# ZHSD-PL-CONNS.net
KiCad netlist of a schematic drawn in Altium Designer
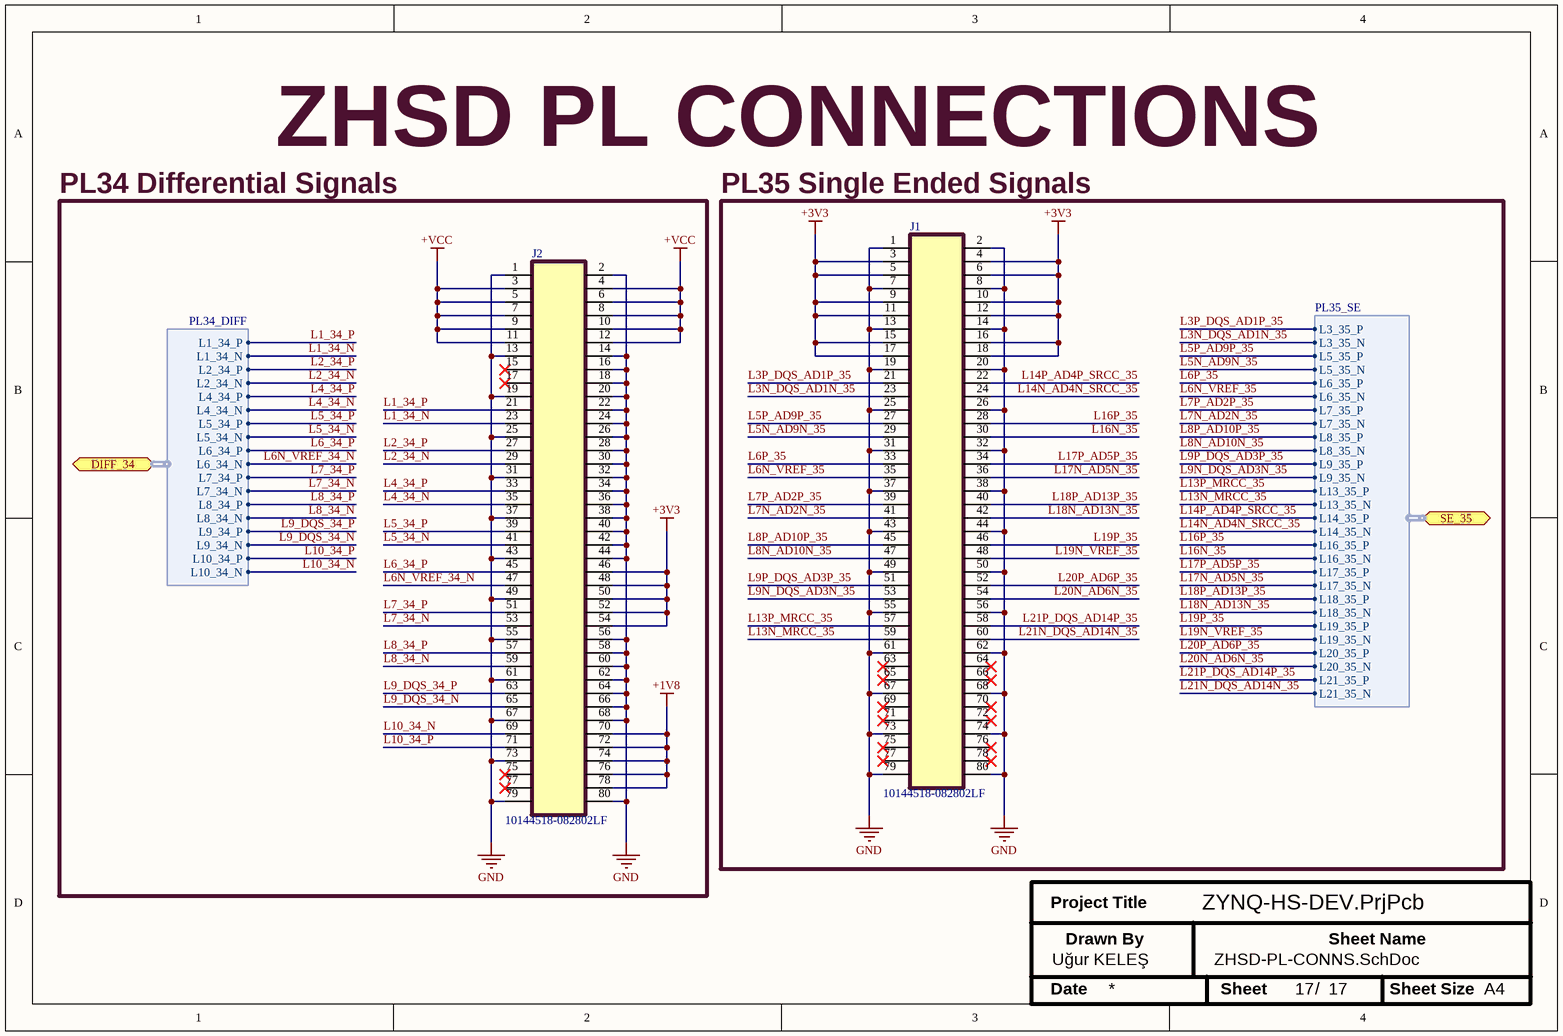
[diagram p0: ZHSD-PL-CONNS.SchDoc]

(export (version "E")
  (design (tool "Eeschema 10.0.6"))
  (components
    (comp (ref "J1")
      (value "10144518-082802LF")
      (footprint "10144518-082802LF")
      (description "BergStak® Lite 0.80mm, Board-to-Board Connector, 80 Positions, Dual Row, Vertical Header")
      (fields (field (name "MANUFACTURER") "Amphenol"))
      (libsource (lib "UK_Library") (part "10144518-082802LF"))
    )
    (comp (ref "J2")
      (value "10144518-082802LF")
      (footprint "10144518-082802LF")
      (description "BergStak® Lite 0.80mm, Board-to-Board Connector, 80 Positions, Dual Row, Vertical Header")
      (fields (field (name "MANUFACTURER") "Amphenol"))
      (libsource (lib "UK_Library") (part "10144518-082802LF"))
    )
  )
  (nets
    (net (code "3") (name "+1V8") (class "Default")
      (node (ref "J2") (pin "70") (pintype "passive"))
      (node (ref "J2") (pin "72") (pintype "passive"))
      (node (ref "J2") (pin "74") (pintype "passive"))
      (node (ref "J2") (pin "76") (pintype "passive"))
      (node (ref "J2") (pin "78") (pintype "passive"))
    )
    (net (code "4") (name "+3V3") (class "Default")
      (node (ref "J1") (pin "10") (pintype "passive"))
      (node (ref "J1") (pin "11") (pintype "passive"))
      (node (ref "J1") (pin "12") (pintype "passive"))
      (node (ref "J1") (pin "15") (pintype "passive"))
      (node (ref "J1") (pin "16") (pintype "passive"))
      (node (ref "J1") (pin "17") (pintype "passive"))
      (node (ref "J1") (pin "18") (pintype "passive"))
      (node (ref "J1") (pin "3") (pintype "passive"))
      (node (ref "J1") (pin "4") (pintype "passive"))
      (node (ref "J1") (pin "5") (pintype "passive"))
      (node (ref "J1") (pin "6") (pintype "passive"))
      (node (ref "J1") (pin "9") (pintype "passive"))
      (node (ref "J2") (pin "46") (pintype "passive"))
      (node (ref "J2") (pin "48") (pintype "passive"))
      (node (ref "J2") (pin "50") (pintype "passive"))
      (node (ref "J2") (pin "52") (pintype "passive"))
      (node (ref "J2") (pin "54") (pintype "passive"))
    )
    (net (code "5") (name "+VCC") (class "Default")
      (node (ref "J2") (pin "10") (pintype "passive"))
      (node (ref "J2") (pin "11") (pintype "passive"))
      (node (ref "J2") (pin "12") (pintype "passive"))
      (node (ref "J2") (pin "3") (pintype "passive"))
      (node (ref "J2") (pin "4") (pintype "passive"))
      (node (ref "J2") (pin "5") (pintype "passive"))
      (node (ref "J2") (pin "6") (pintype "passive"))
      (node (ref "J2") (pin "7") (pintype "passive"))
      (node (ref "J2") (pin "8") (pintype "passive"))
      (node (ref "J2") (pin "9") (pintype "passive"))
    )
    (net (code "6") (name "/L1_34_N") (class "Default") (node (ref "J2") (pin "23") (pintype "passive")))
    (net (code "7") (name "/L1_34_P") (class "Default") (node (ref "J2") (pin "21") (pintype "passive")))
    (net (code "8") (name "/L2_34_N") (class "Default") (node (ref "J2") (pin "29") (pintype "passive")))
    (net (code "9") (name "/L2_34_P") (class "Default") (node (ref "J2") (pin "27") (pintype "passive")))
    (net (code "10") (name "/L3N_DQS_AD1N_35") (class "Default")
      (node (ref "J1") (pin "23") (pintype "passive"))
    )
    (net (code "11") (name "/L3P_DQS_AD1P_35") (class "Default")
      (node (ref "J1") (pin "21") (pintype "passive"))
    )
    (net (code "12") (name "/L4_34_N") (class "Default") (node (ref "J2") (pin "35") (pintype "passive")))
    (net (code "13") (name "/L4_34_P") (class "Default") (node (ref "J2") (pin "33") (pintype "passive")))
    (net (code "14") (name "/L5N_AD9N_35") (class "Default") (node (ref "J1") (pin "29") (pintype "passive")))
    (net (code "15") (name "/L5P_AD9P_35") (class "Default") (node (ref "J1") (pin "27") (pintype "passive")))
    (net (code "16") (name "/L5_34_N") (class "Default") (node (ref "J2") (pin "41") (pintype "passive")))
    (net (code "17") (name "/L5_34_P") (class "Default") (node (ref "J2") (pin "39") (pintype "passive")))
    (net (code "18") (name "/L6N_VREF_34_N") (class "Default")
      (node (ref "J2") (pin "47") (pintype "passive"))
    )
    (net (code "19") (name "/L6N_VREF_35") (class "Default") (node (ref "J1") (pin "35") (pintype "passive")))
    (net (code "20") (name "/L6P_35") (class "Default") (node (ref "J1") (pin "33") (pintype "passive")))
    (net (code "21") (name "/L6_34_P") (class "Default") (node (ref "J2") (pin "45") (pintype "passive")))
    (net (code "22") (name "/L7N_AD2N_35") (class "Default") (node (ref "J1") (pin "41") (pintype "passive")))
    (net (code "23") (name "/L7P_AD2P_35") (class "Default") (node (ref "J1") (pin "39") (pintype "passive")))
    (net (code "24") (name "/L7_34_N") (class "Default") (node (ref "J2") (pin "53") (pintype "passive")))
    (net (code "25") (name "/L7_34_P") (class "Default") (node (ref "J2") (pin "51") (pintype "passive")))
    (net (code "26") (name "/L8N_AD10N_35") (class "Default")
      (node (ref "J1") (pin "47") (pintype "passive"))
    )
    (net (code "27") (name "/L8P_AD10P_35") (class "Default")
      (node (ref "J1") (pin "45") (pintype "passive"))
    )
    (net (code "28") (name "/L8_34_N") (class "Default") (node (ref "J2") (pin "59") (pintype "passive")))
    (net (code "29") (name "/L8_34_P") (class "Default") (node (ref "J2") (pin "57") (pintype "passive")))
    (net (code "30") (name "/L9N_DQS_AD3N_35") (class "Default")
      (node (ref "J1") (pin "53") (pintype "passive"))
    )
    (net (code "31") (name "/L9P_DQS_AD3P_35") (class "Default")
      (node (ref "J1") (pin "51") (pintype "passive"))
    )
    (net (code "32") (name "/L9_DQS_34_N") (class "Default") (node (ref "J2") (pin "65") (pintype "passive")))
    (net (code "33") (name "/L9_DQS_34_P") (class "Default") (node (ref "J2") (pin "63") (pintype "passive")))
    (net (code "34") (name "/L10_34_N") (class "Default") (node (ref "J2") (pin "69") (pintype "passive")))
    (net (code "35") (name "/L10_34_P") (class "Default") (node (ref "J2") (pin "71") (pintype "passive")))
    (net (code "36") (name "/L13N_MRCC_35") (class "Default")
      (node (ref "J1") (pin "59") (pintype "passive"))
    )
    (net (code "37") (name "/L13P_MRCC_35") (class "Default")
      (node (ref "J1") (pin "57") (pintype "passive"))
    )
    (net (code "38") (name "/L14N_AD4N_SRCC_35") (class "Default")
      (node (ref "J1") (pin "24") (pintype "passive"))
    )
    (net (code "39") (name "/L14P_AD4P_SRCC_35") (class "Default")
      (node (ref "J1") (pin "22") (pintype "passive"))
    )
    (net (code "40") (name "/L16N_35") (class "Default") (node (ref "J1") (pin "30") (pintype "passive")))
    (net (code "41") (name "/L16P_35") (class "Default") (node (ref "J1") (pin "28") (pintype "passive")))
    (net (code "42") (name "/L17N_AD5N_35") (class "Default")
      (node (ref "J1") (pin "36") (pintype "passive"))
    )
    (net (code "43") (name "/L17P_AD5P_35") (class "Default")
      (node (ref "J1") (pin "34") (pintype "passive"))
    )
    (net (code "44") (name "/L18N_AD13N_35") (class "Default")
      (node (ref "J1") (pin "42") (pintype "passive"))
    )
    (net (code "45") (name "/L18P_AD13P_35") (class "Default")
      (node (ref "J1") (pin "40") (pintype "passive"))
    )
    (net (code "46") (name "/L19N_VREF_35") (class "Default")
      (node (ref "J1") (pin "48") (pintype "passive"))
    )
    (net (code "47") (name "/L19P_35") (class "Default") (node (ref "J1") (pin "46") (pintype "passive")))
    (net (code "48") (name "/L20N_AD6N_35") (class "Default")
      (node (ref "J1") (pin "54") (pintype "passive"))
    )
    (net (code "49") (name "/L20P_AD6P_35") (class "Default")
      (node (ref "J1") (pin "52") (pintype "passive"))
    )
    (net (code "50") (name "/L21N_DQS_AD14N_35") (class "Default")
      (node (ref "J1") (pin "60") (pintype "passive"))
    )
    (net (code "51") (name "/L21P_DQS_AD14P_35") (class "Default")
      (node (ref "J1") (pin "58") (pintype "passive"))
    )
    (net (code "54") (name "GND") (class "Default")
      (node (ref "J1") (pin "1") (pintype "passive"))
      (node (ref "J1") (pin "13") (pintype "passive"))
      (node (ref "J1") (pin "14") (pintype "passive"))
      (node (ref "J1") (pin "19") (pintype "passive"))
      (node (ref "J1") (pin "2") (pintype "passive"))
      (node (ref "J1") (pin "20") (pintype "passive"))
      (node (ref "J1") (pin "25") (pintype "passive"))
      (node (ref "J1") (pin "26") (pintype "passive"))
      (node (ref "J1") (pin "31") (pintype "passive"))
      (node (ref "J1") (pin "32") (pintype "passive"))
      (node (ref "J1") (pin "37") (pintype "passive"))
      (node (ref "J1") (pin "38") (pintype "passive"))
      (node (ref "J1") (pin "43") (pintype "passive"))
      (node (ref "J1") (pin "44") (pintype "passive"))
      (node (ref "J1") (pin "49") (pintype "passive"))
      (node (ref "J1") (pin "50") (pintype "passive"))
      (node (ref "J1") (pin "55") (pintype "passive"))
      (node (ref "J1") (pin "56") (pintype "passive"))
      (node (ref "J1") (pin "61") (pintype "passive"))
      (node (ref "J1") (pin "62") (pintype "passive"))
      (node (ref "J1") (pin "67") (pintype "passive"))
      (node (ref "J1") (pin "68") (pintype "passive"))
      (node (ref "J1") (pin "7") (pintype "passive"))
      (node (ref "J1") (pin "73") (pintype "passive"))
      (node (ref "J1") (pin "74") (pintype "passive"))
      (node (ref "J1") (pin "79") (pintype "passive"))
      (node (ref "J1") (pin "8") (pintype "passive"))
      (node (ref "J1") (pin "80") (pintype "passive"))
      (node (ref "J2") (pin "1") (pintype "passive"))
      (node (ref "J2") (pin "13") (pintype "passive"))
      (node (ref "J2") (pin "14") (pintype "passive"))
      (node (ref "J2") (pin "16") (pintype "passive"))
      (node (ref "J2") (pin "18") (pintype "passive"))
      (node (ref "J2") (pin "19") (pintype "passive"))
      (node (ref "J2") (pin "2") (pintype "passive"))
      (node (ref "J2") (pin "20") (pintype "passive"))
      (node (ref "J2") (pin "22") (pintype "passive"))
      (node (ref "J2") (pin "24") (pintype "passive"))
      (node (ref "J2") (pin "25") (pintype "passive"))
      (node (ref "J2") (pin "26") (pintype "passive"))
      (node (ref "J2") (pin "28") (pintype "passive"))
      (node (ref "J2") (pin "30") (pintype "passive"))
      (node (ref "J2") (pin "31") (pintype "passive"))
      (node (ref "J2") (pin "32") (pintype "passive"))
      (node (ref "J2") (pin "34") (pintype "passive"))
      (node (ref "J2") (pin "36") (pintype "passive"))
      (node (ref "J2") (pin "37") (pintype "passive"))
      (node (ref "J2") (pin "38") (pintype "passive"))
      (node (ref "J2") (pin "40") (pintype "passive"))
      (node (ref "J2") (pin "42") (pintype "passive"))
      (node (ref "J2") (pin "43") (pintype "passive"))
      (node (ref "J2") (pin "44") (pintype "passive"))
      (node (ref "J2") (pin "49") (pintype "passive"))
      (node (ref "J2") (pin "55") (pintype "passive"))
      (node (ref "J2") (pin "56") (pintype "passive"))
      (node (ref "J2") (pin "58") (pintype "passive"))
      (node (ref "J2") (pin "60") (pintype "passive"))
      (node (ref "J2") (pin "61") (pintype "passive"))
      (node (ref "J2") (pin "62") (pintype "passive"))
      (node (ref "J2") (pin "64") (pintype "passive"))
      (node (ref "J2") (pin "66") (pintype "passive"))
      (node (ref "J2") (pin "67") (pintype "passive"))
      (node (ref "J2") (pin "68") (pintype "passive"))
      (node (ref "J2") (pin "73") (pintype "passive"))
      (node (ref "J2") (pin "79") (pintype "passive"))
      (node (ref "J2") (pin "80") (pintype "passive"))
    )
    (net (code "55") (name "unconnected-(J1-Pad63)") (class "Default")
      (node (ref "J1") (pin "63") (pintype "passive+no_connect"))
    )
    (net (code "56") (name "unconnected-(J1-Pad64)") (class "Default")
      (node (ref "J1") (pin "64") (pintype "passive+no_connect"))
    )
    (net (code "57") (name "unconnected-(J1-Pad65)") (class "Default")
      (node (ref "J1") (pin "65") (pintype "passive+no_connect"))
    )
    (net (code "58") (name "unconnected-(J1-Pad66)") (class "Default")
      (node (ref "J1") (pin "66") (pintype "passive+no_connect"))
    )
    (net (code "59") (name "unconnected-(J1-Pad69)") (class "Default")
      (node (ref "J1") (pin "69") (pintype "passive+no_connect"))
    )
    (net (code "60") (name "unconnected-(J1-Pad70)") (class "Default")
      (node (ref "J1") (pin "70") (pintype "passive+no_connect"))
    )
    (net (code "61") (name "unconnected-(J1-Pad71)") (class "Default")
      (node (ref "J1") (pin "71") (pintype "passive+no_connect"))
    )
    (net (code "62") (name "unconnected-(J1-Pad72)") (class "Default")
      (node (ref "J1") (pin "72") (pintype "passive+no_connect"))
    )
    (net (code "63") (name "unconnected-(J1-Pad75)") (class "Default")
      (node (ref "J1") (pin "75") (pintype "passive+no_connect"))
    )
    (net (code "64") (name "unconnected-(J1-Pad76)") (class "Default")
      (node (ref "J1") (pin "76") (pintype "passive+no_connect"))
    )
    (net (code "65") (name "unconnected-(J1-Pad77)") (class "Default")
      (node (ref "J1") (pin "77") (pintype "passive+no_connect"))
    )
    (net (code "66") (name "unconnected-(J1-Pad78)") (class "Default")
      (node (ref "J1") (pin "78") (pintype "passive+no_connect"))
    )
    (net (code "67") (name "unconnected-(J2-Pad15)") (class "Default")
      (node (ref "J2") (pin "15") (pintype "passive+no_connect"))
    )
    (net (code "68") (name "unconnected-(J2-Pad17)") (class "Default")
      (node (ref "J2") (pin "17") (pintype "passive+no_connect"))
    )
    (net (code "69") (name "unconnected-(J2-Pad75)") (class "Default")
      (node (ref "J2") (pin "75") (pintype "passive+no_connect"))
    )
    (net (code "70") (name "unconnected-(J2-Pad77)") (class "Default")
      (node (ref "J2") (pin "77") (pintype "passive+no_connect"))
    )
  )
)
